# rev_002.net
KiCad netlist of a schematic drawn in EAGLE
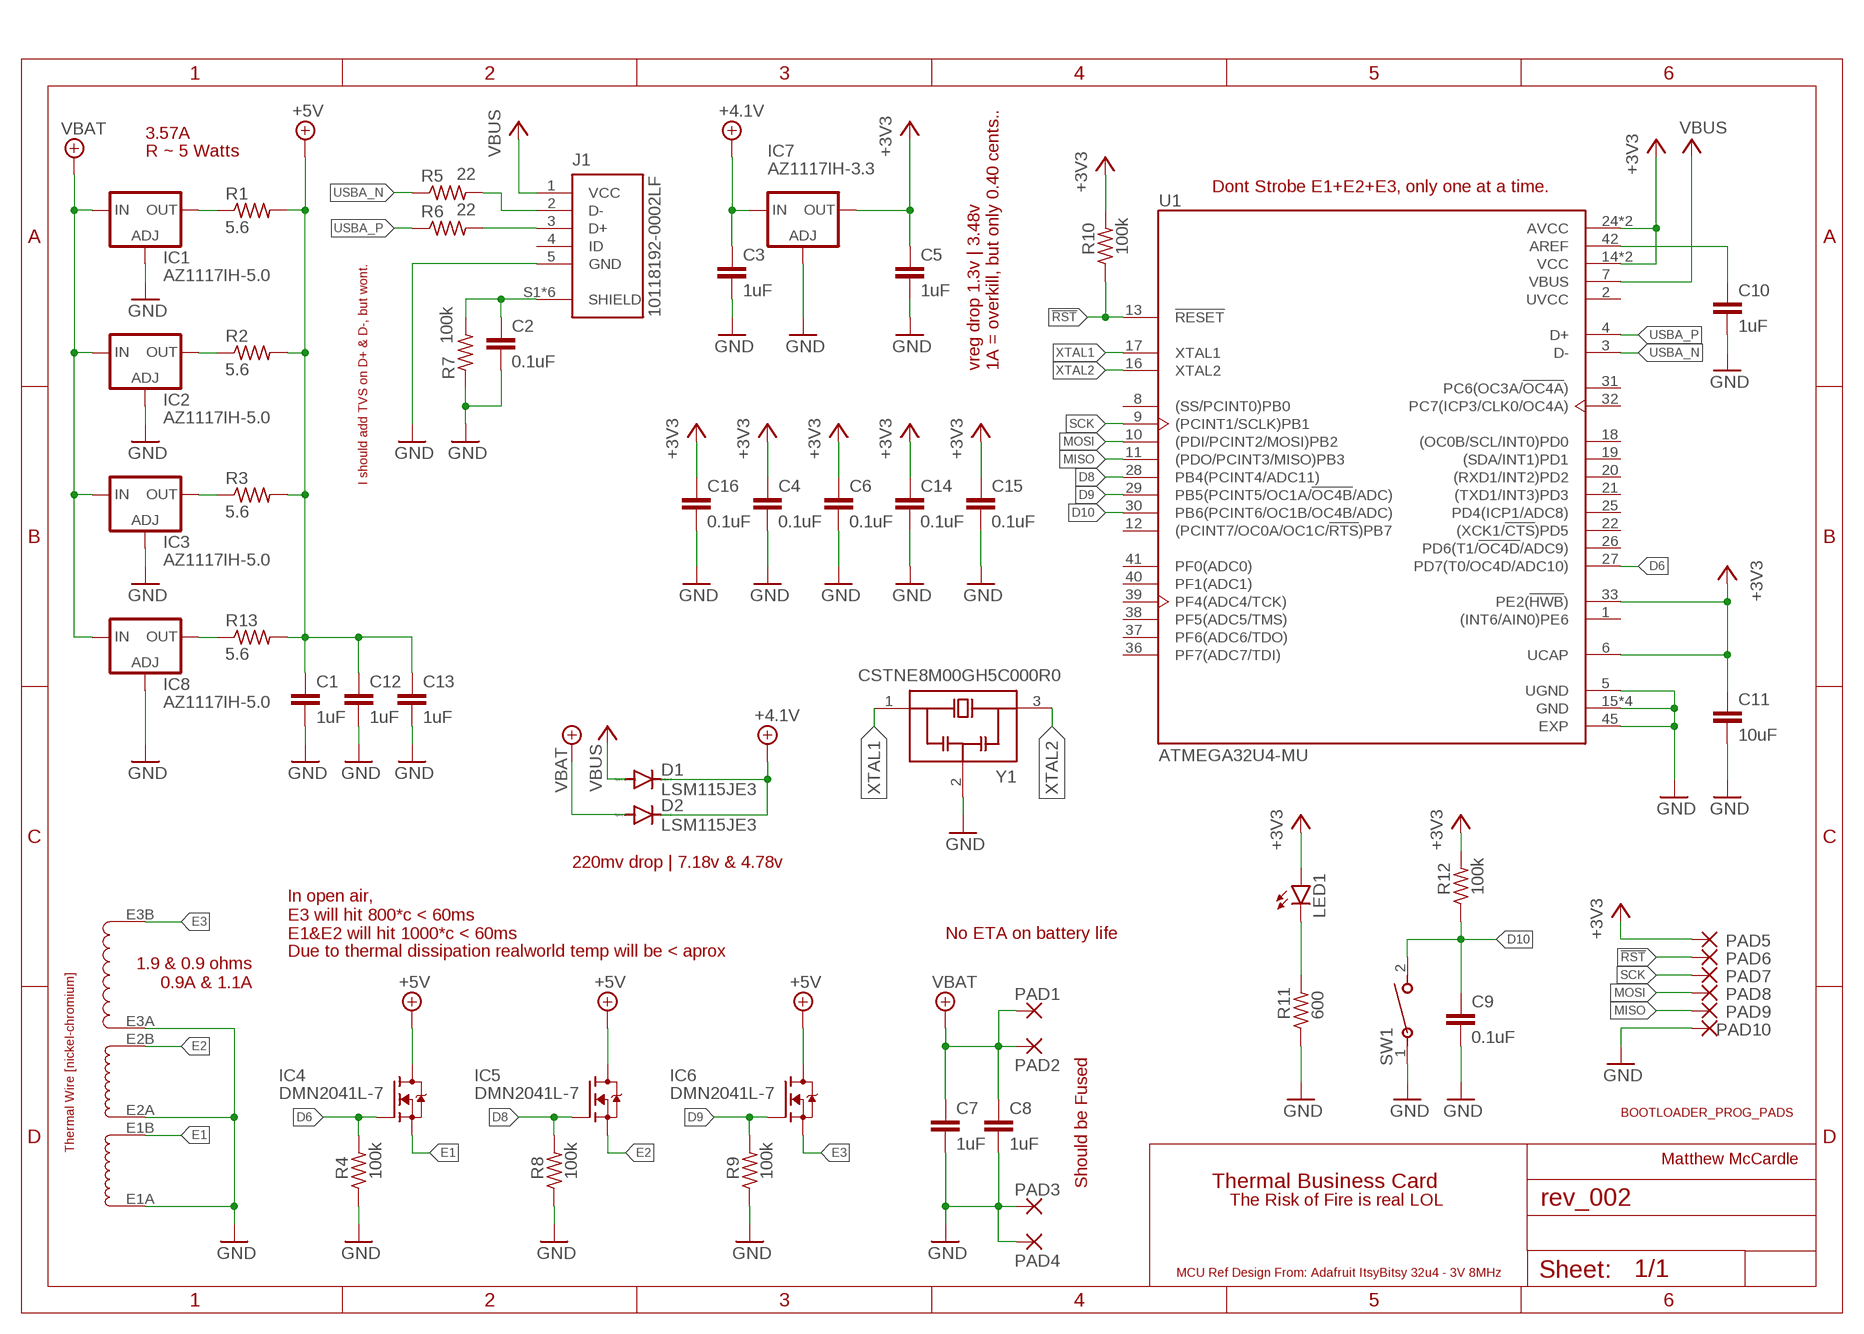
[diagram p0: schematic, sheet 1]

(export (version "E")
  (design (tool "Eeschema 10.0.6"))
  (components
    (comp (ref "C1")
      (value "1uF")
      (footprint "eagle-import:C0603")
      (libsource (lib "eagle-import") (part "C-EUC0603"))
    )
    (comp (ref "C2")
      (value "0.1uF")
      (footprint "eagle-import:C0603")
      (libsource (lib "eagle-import") (part "C-EUC0603"))
    )
    (comp (ref "C3")
      (value "1uF")
      (footprint "eagle-import:C0603")
      (libsource (lib "eagle-import") (part "C-EUC0603"))
    )
    (comp (ref "C4")
      (value "0.1uF")
      (footprint "eagle-import:C0603")
      (libsource (lib "eagle-import") (part "C-EUC0603"))
    )
    (comp (ref "C5")
      (value "1uF")
      (footprint "eagle-import:C0603")
      (libsource (lib "eagle-import") (part "C-EUC0603"))
    )
    (comp (ref "C6")
      (value "0.1uF")
      (footprint "eagle-import:C0603")
      (libsource (lib "eagle-import") (part "C-EUC0603"))
    )
    (comp (ref "C7")
      (value "1uF")
      (footprint "eagle-import:C0603")
      (libsource (lib "eagle-import") (part "C-EUC0603"))
    )
    (comp (ref "C8")
      (value "1uF")
      (footprint "eagle-import:C0603")
      (libsource (lib "eagle-import") (part "C-EUC0603"))
    )
    (comp (ref "C9")
      (value "0.1uF")
      (footprint "eagle-import:C0603")
      (libsource (lib "eagle-import") (part "C-EUC0603"))
    )
    (comp (ref "C10")
      (value "1uF")
      (footprint "eagle-import:C0603")
      (libsource (lib "eagle-import") (part "C-EUC0603"))
    )
    (comp (ref "C11")
      (value "10uF")
      (footprint "eagle-import:C0603")
      (libsource (lib "eagle-import") (part "C-EUC0603"))
    )
    (comp (ref "C12")
      (value "1uF")
      (footprint "eagle-import:C0603")
      (libsource (lib "eagle-import") (part "C-EUC0603"))
    )
    (comp (ref "C13")
      (value "1uF")
      (footprint "eagle-import:C0603")
      (libsource (lib "eagle-import") (part "C-EUC0603"))
    )
    (comp (ref "C14")
      (value "0.1uF")
      (footprint "eagle-import:C0603")
      (libsource (lib "eagle-import") (part "C-EUC0603"))
    )
    (comp (ref "C15")
      (value "0.1uF")
      (footprint "eagle-import:C0603")
      (libsource (lib "eagle-import") (part "C-EUC0603"))
    )
    (comp (ref "C16")
      (value "0.1uF")
      (footprint "eagle-import:C0603")
      (libsource (lib "eagle-import") (part "C-EUC0603"))
    )
    (comp (ref "D1")
      (value "LSM115JE3")
      (footprint "eagle-import:DO214BA")
      (libsource (lib "eagle-import") (part "DIODE-DO214BA"))
    )
    (comp (ref "D2")
      (value "LSM115JE3")
      (footprint "eagle-import:DO214BA")
      (libsource (lib "eagle-import") (part "DIODE-DO214BA"))
    )
    (comp (ref "IC1")
      (value "AZ1117IH-5.0")
      (footprint "eagle-import:SOT223")
      (libsource (lib "eagle-import") (part "AZ1117IH"))
    )
    (comp (ref "IC2")
      (value "AZ1117IH-5.0")
      (footprint "eagle-import:SOT223")
      (libsource (lib "eagle-import") (part "AZ1117IH"))
    )
    (comp (ref "IC3")
      (value "AZ1117IH-5.0")
      (footprint "eagle-import:SOT223")
      (libsource (lib "eagle-import") (part "AZ1117IH"))
    )
    (comp (ref "IC4")
      (value "DMN2041L-7")
      (footprint "eagle-import:SOT23")
      (libsource (lib "eagle-import") (part "DS31126"))
    )
    (comp (ref "IC5")
      (value "DMN2041L-7")
      (footprint "eagle-import:SOT23")
      (libsource (lib "eagle-import") (part "DS31126"))
    )
    (comp (ref "IC6")
      (value "DMN2041L-7")
      (footprint "eagle-import:SOT23")
      (libsource (lib "eagle-import") (part "DS31126"))
    )
    (comp (ref "IC7")
      (value "AZ1117IH-3.3")
      (footprint "eagle-import:SOT223")
      (libsource (lib "eagle-import") (part "AZ1117IH"))
    )
    (comp (ref "IC8")
      (value "AZ1117IH-5.0")
      (footprint "eagle-import:SOT223")
      (libsource (lib "eagle-import") (part "AZ1117IH"))
    )
    (comp (ref "J1")
      (value "10118192-0002LF")
      (footprint "eagle-import:AMPHENOL_10118192-0002LF")
      (fields (field (name "DIGI-KEY_PART_NUMBER") "609-5379-1-ND") (field (name "MF") "Amphenol ICC (FCI)"))
      (libsource (lib "eagle-import") (part "10118192-0002LF"))
    )
    (comp (ref "LED1")
      (value "LEDSML0603")
      (footprint "eagle-import:SML0603")
      (libsource (lib "eagle-import") (part "LEDSML0603"))
    )
    (comp (ref "NICR1")
      (value "HOT_WIRE")
      (footprint "eagle-import:LAYOUT_A")
      (libsource (lib "eagle-import") (part "HOT_WIRE"))
    )
    (comp (ref "PAD1")
      (value "WIREPADSMD5-2,5")
      (footprint "eagle-import:5-2,5")
      (libsource (lib "eagle-import") (part "WIREPADSMD5-2,5"))
    )
    (comp (ref "PAD2")
      (value "WIREPAD2,54/0,9")
      (footprint "eagle-import:2,54_0,9")
      (libsource (lib "eagle-import") (part "WIREPAD2,54/0,9"))
    )
    (comp (ref "PAD3")
      (value "WIREPAD2,54/0,9")
      (footprint "eagle-import:2,54_0,9")
      (libsource (lib "eagle-import") (part "WIREPAD2,54/0,9"))
    )
    (comp (ref "PAD4")
      (value "WIREPADSMD5-2,5")
      (footprint "eagle-import:5-2,5")
      (libsource (lib "eagle-import") (part "WIREPADSMD5-2,5"))
    )
    (comp (ref "PAD5")
      (value "WIREPADSMD1,27-254")
      (footprint "eagle-import:SMD1,27-2,54")
      (libsource (lib "eagle-import") (part "WIREPADSMD1,27-254"))
    )
    (comp (ref "PAD6")
      (value "WIREPADSMD1,27-254")
      (footprint "eagle-import:SMD1,27-2,54")
      (libsource (lib "eagle-import") (part "WIREPADSMD1,27-254"))
    )
    (comp (ref "PAD7")
      (value "WIREPADSMD1,27-254")
      (footprint "eagle-import:SMD1,27-2,54")
      (libsource (lib "eagle-import") (part "WIREPADSMD1,27-254"))
    )
    (comp (ref "PAD8")
      (value "WIREPADSMD1,27-254")
      (footprint "eagle-import:SMD1,27-2,54")
      (libsource (lib "eagle-import") (part "WIREPADSMD1,27-254"))
    )
    (comp (ref "PAD9")
      (value "WIREPADSMD1,27-254")
      (footprint "eagle-import:SMD1,27-2,54")
      (libsource (lib "eagle-import") (part "WIREPADSMD1,27-254"))
    )
    (comp (ref "PAD10")
      (value "WIREPADSMD1,27-254")
      (footprint "eagle-import:SMD1,27-2,54")
      (libsource (lib "eagle-import") (part "WIREPADSMD1,27-254"))
    )
    (comp (ref "R1")
      (value "5.6")
      (footprint "eagle-import:R2512")
      (libsource (lib "eagle-import") (part "R-US_R2512"))
    )
    (comp (ref "R2")
      (value "5.6")
      (footprint "eagle-import:R2512")
      (libsource (lib "eagle-import") (part "R-US_R2512"))
    )
    (comp (ref "R3")
      (value "5.6")
      (footprint "eagle-import:R2512")
      (libsource (lib "eagle-import") (part "R-US_R2512"))
    )
    (comp (ref "R4")
      (value "100k")
      (footprint "eagle-import:R0603")
      (libsource (lib "eagle-import") (part "R-US_R0603"))
    )
    (comp (ref "R5")
      (value "22")
      (footprint "eagle-import:R0603")
      (libsource (lib "eagle-import") (part "R-US_R0603"))
    )
    (comp (ref "R6")
      (value "22")
      (footprint "eagle-import:R0603")
      (libsource (lib "eagle-import") (part "R-US_R0603"))
    )
    (comp (ref "R7")
      (value "100k")
      (footprint "eagle-import:R0603")
      (libsource (lib "eagle-import") (part "R-US_R0603"))
    )
    (comp (ref "R8")
      (value "100k")
      (footprint "eagle-import:R0603")
      (libsource (lib "eagle-import") (part "R-US_R0603"))
    )
    (comp (ref "R9")
      (value "100k")
      (footprint "eagle-import:R0603")
      (libsource (lib "eagle-import") (part "R-US_R0603"))
    )
    (comp (ref "R10")
      (value "100k")
      (footprint "eagle-import:R0603")
      (libsource (lib "eagle-import") (part "R-US_R0603"))
    )
    (comp (ref "R11")
      (value "600")
      (footprint "eagle-import:R0603")
      (libsource (lib "eagle-import") (part "R-US_R0603"))
    )
    (comp (ref "R12")
      (value "100k")
      (footprint "eagle-import:R0603")
      (libsource (lib "eagle-import") (part "R-US_R0603"))
    )
    (comp (ref "R13")
      (value "5.6")
      (footprint "eagle-import:R2512")
      (libsource (lib "eagle-import") (part "R-US_R2512"))
    )
    (comp (ref "SW1")
      (value "B3AL-1000P")
      (footprint "eagle-import:SW_B3AL_OMR")
      (fields (field (name "COPYRIGHT") "Copyright (C) 2021 Ultra Librarian. All rights reserved."))
      (libsource (lib "eagle-import") (part "B3AL-1000P"))
    )
    (comp (ref "U1")
      (value "ATMEGA32U4-MU")
      (footprint "eagle-import:QFN50P700X700X100-45N")
      (fields
        (field (name "DIGI-KEY_PART_NUMBER") "2156-ATMEGA32U4-MUR-ND")
        (field (name "MF") "Microchip Technology / Atmel")
      )
      (libsource (lib "eagle-import") (part "ATMEGA32U4-MU"))
    )
    (comp (ref "Y1")
      (value "CSTNE8M00GH5C000R0")
      (footprint "eagle-import:OSC_CSTNE8M00GH5C000R0")
      (fields (field (name "DIGI-KEY_PART_NUMBER") "490-17961-1-ND") (field (name "MF") "Murata"))
      (libsource (lib "eagle-import") (part "CSTNE8M00GH5C000R0"))
    )
  )
  (nets
    (net (code "1") (name "+3V3") (class "Default")
      (node (ref "C11") (pin "1") (pinfunction "1_1") (pintype "passive"))
      (node (ref "C14") (pin "1") (pinfunction "1_1") (pintype "passive"))
      (node (ref "C15") (pin "1") (pinfunction "1_1") (pintype "passive"))
      (node (ref "C16") (pin "1") (pinfunction "1_1") (pintype "passive"))
      (node (ref "C4") (pin "1") (pinfunction "1_1") (pintype "passive"))
      (node (ref "C5") (pin "1") (pinfunction "1_1") (pintype "passive"))
      (node (ref "C6") (pin "1") (pinfunction "1_1") (pintype "passive"))
      (node (ref "IC7") (pin "2") (pinfunction "OUT_2") (pintype "passive"))
      (node (ref "IC7") (pin "4") (pinfunction "OUT_4") (pintype "passive"))
      (node (ref "LED1") (pin "A") (pinfunction "A_A") (pintype "passive"))
      (node (ref "PAD5") (pin "1") (pinfunction "P_1") (pintype "passive"))
      (node (ref "R10") (pin "2") (pinfunction "2_2") (pintype "passive"))
      (node (ref "R12") (pin "2") (pinfunction "2_2") (pintype "passive"))
      (node (ref "U1") (pin "14") (pinfunction "VCC_14") (pintype "power_in"))
      (node (ref "U1") (pin "24") (pinfunction "AVCC_24") (pintype "power_in"))
      (node (ref "U1") (pin "33") (pinfunction "PE2(~{HWB})_33") (pintype "bidirectional"))
      (node (ref "U1") (pin "34") (pinfunction "VCC_34") (pintype "power_in"))
      (node (ref "U1") (pin "44") (pinfunction "AVCC_44") (pintype "power_in"))
      (node (ref "U1") (pin "6") (pinfunction "UCAP_6") (pintype "passive"))
    )
    (net (code "2") (name "+4.1V") (class "Default")
      (node (ref "C3") (pin "1") (pinfunction "1_1") (pintype "passive"))
      (node (ref "D1") (pin "C") (pinfunction "C_C") (pintype "passive"))
      (node (ref "D2") (pin "C") (pinfunction "C_C") (pintype "passive"))
      (node (ref "IC7") (pin "3") (pinfunction "IN_3") (pintype "input"))
    )
    (net (code "3") (name "+5V") (class "Default")
      (node (ref "C1") (pin "1") (pinfunction "1_1") (pintype "passive"))
      (node (ref "C12") (pin "1") (pinfunction "1_1") (pintype "passive"))
      (node (ref "C13") (pin "1") (pinfunction "1_1") (pintype "passive"))
      (node (ref "IC4") (pin "D") (pinfunction "D_D") (pintype "passive"))
      (node (ref "IC5") (pin "D") (pinfunction "D_D") (pintype "passive"))
      (node (ref "IC6") (pin "D") (pinfunction "D_D") (pintype "passive"))
      (node (ref "R1") (pin "2") (pinfunction "2_2") (pintype "passive"))
      (node (ref "R13") (pin "2") (pinfunction "2_2") (pintype "passive"))
      (node (ref "R2") (pin "2") (pinfunction "2_2") (pintype "passive"))
      (node (ref "R3") (pin "2") (pinfunction "2_2") (pintype "passive"))
    )
    (net (code "4") (name "/UVCC") (class "Default")
      (node (ref "U1") (pin "2") (pinfunction "UVCC_2") (pintype "power_in"))
    )
    (net (code "5") (name "/~{RST}") (class "Default")
      (node (ref "PAD6") (pin "1") (pinfunction "P_1") (pintype "passive"))
      (node (ref "R10") (pin "1") (pinfunction "1_1") (pintype "passive"))
      (node (ref "U1") (pin "13") (pinfunction "~{RESET}_13") (pintype "input"))
    )
    (net (code "6") (name "D6") (class "Default")
      (node (ref "IC4") (pin "G") (pinfunction "G_G") (pintype "passive"))
      (node (ref "R4") (pin "2") (pinfunction "2_2") (pintype "passive"))
      (node (ref "U1") (pin "27") (pinfunction "PD7(T0/OC4D/ADC10)_27") (pintype "bidirectional"))
    )
    (net (code "7") (name "D8") (class "Default")
      (node (ref "IC5") (pin "G") (pinfunction "G_G") (pintype "passive"))
      (node (ref "R8") (pin "2") (pinfunction "2_2") (pintype "passive"))
      (node (ref "U1") (pin "28") (pinfunction "PB4(PCINT4/ADC11)_28") (pintype "bidirectional"))
    )
    (net (code "8") (name "D9") (class "Default")
      (node (ref "IC6") (pin "G") (pinfunction "G_G") (pintype "passive"))
      (node (ref "R9") (pin "2") (pinfunction "2_2") (pintype "passive"))
      (node (ref "U1") (pin "29") (pinfunction "PB5(PCINT5/OC1A/~{OC4B}/ADC)_29") (pintype "bidirectional"))
    )
    (net (code "9") (name "D10") (class "Default")
      (node (ref "C9") (pin "1") (pinfunction "1_1") (pintype "passive"))
      (node (ref "R12") (pin "1") (pinfunction "1_1") (pintype "passive"))
      (node (ref "SW1") (pin "2") (pinfunction "2_2") (pintype "passive"))
      (node (ref "U1") (pin "30") (pinfunction "PB6(PCINT6/OC1B/OC4B/ADC)_30") (pintype "bidirectional"))
    )
    (net (code "10") (name "E1") (class "Default")
      (node (ref "IC4") (pin "S") (pinfunction "S_S") (pintype "passive"))
      (node (ref "NICR1") (pin "E1B") (pinfunction "P$2_E1B") (pintype "bidirectional"))
    )
    (net (code "11") (name "E2") (class "Default")
      (node (ref "IC5") (pin "S") (pinfunction "S_S") (pintype "passive"))
      (node (ref "NICR1") (pin "E2B") (pinfunction "P$2_E2B") (pintype "bidirectional"))
    )
    (net (code "12") (name "E3") (class "Default")
      (node (ref "IC6") (pin "S") (pinfunction "S_S") (pintype "passive"))
      (node (ref "NICR1") (pin "E3B") (pinfunction "P$2_E3B") (pintype "bidirectional"))
    )
    (net (code "13") (name "GND") (class "Default")
      (node (ref "C1") (pin "2") (pinfunction "2_2") (pintype "passive"))
      (node (ref "C10") (pin "2") (pinfunction "2_2") (pintype "passive"))
      (node (ref "C11") (pin "2") (pinfunction "2_2") (pintype "passive"))
      (node (ref "C12") (pin "2") (pinfunction "2_2") (pintype "passive"))
      (node (ref "C13") (pin "2") (pinfunction "2_2") (pintype "passive"))
      (node (ref "C14") (pin "2") (pinfunction "2_2") (pintype "passive"))
      (node (ref "C15") (pin "2") (pinfunction "2_2") (pintype "passive"))
      (node (ref "C16") (pin "2") (pinfunction "2_2") (pintype "passive"))
      (node (ref "C2") (pin "2") (pinfunction "2_2") (pintype "passive"))
      (node (ref "C3") (pin "2") (pinfunction "2_2") (pintype "passive"))
      (node (ref "C4") (pin "2") (pinfunction "2_2") (pintype "passive"))
      (node (ref "C5") (pin "2") (pinfunction "2_2") (pintype "passive"))
      (node (ref "C6") (pin "2") (pinfunction "2_2") (pintype "passive"))
      (node (ref "C7") (pin "2") (pinfunction "2_2") (pintype "passive"))
      (node (ref "C8") (pin "2") (pinfunction "2_2") (pintype "passive"))
      (node (ref "C9") (pin "2") (pinfunction "2_2") (pintype "passive"))
      (node (ref "IC1") (pin "1") (pinfunction "ADJ_1") (pintype "input"))
      (node (ref "IC2") (pin "1") (pinfunction "ADJ_1") (pintype "input"))
      (node (ref "IC3") (pin "1") (pinfunction "ADJ_1") (pintype "input"))
      (node (ref "IC7") (pin "1") (pinfunction "ADJ_1") (pintype "input"))
      (node (ref "IC8") (pin "1") (pinfunction "ADJ_1") (pintype "input"))
      (node (ref "J1") (pin "5") (pinfunction "GND_5") (pintype "power_in"))
      (node (ref "NICR1") (pin "E1A") (pinfunction "P$1_E1A") (pintype "bidirectional"))
      (node (ref "NICR1") (pin "E2A") (pinfunction "P$1_E2A") (pintype "bidirectional"))
      (node (ref "NICR1") (pin "E3A") (pinfunction "P$1_E3A") (pintype "bidirectional"))
      (node (ref "PAD10") (pin "1") (pinfunction "P_1") (pintype "passive"))
      (node (ref "PAD3") (pin "1") (pinfunction "P_1") (pintype "passive"))
      (node (ref "PAD4") (pin "1") (pinfunction "P_1") (pintype "passive"))
      (node (ref "R11") (pin "1") (pinfunction "1_1") (pintype "passive"))
      (node (ref "R4") (pin "1") (pinfunction "1_1") (pintype "passive"))
      (node (ref "R7") (pin "1") (pinfunction "1_1") (pintype "passive"))
      (node (ref "R8") (pin "1") (pinfunction "1_1") (pintype "passive"))
      (node (ref "R9") (pin "1") (pinfunction "1_1") (pintype "passive"))
      (node (ref "SW1") (pin "1") (pinfunction "1_1") (pintype "passive"))
      (node (ref "U1") (pin "15") (pinfunction "GND_15") (pintype "power_in"))
      (node (ref "U1") (pin "23") (pinfunction "GND_23") (pintype "power_in"))
      (node (ref "U1") (pin "35") (pinfunction "GND_35") (pintype "power_in"))
      (node (ref "U1") (pin "43") (pinfunction "GND_43") (pintype "power_in"))
      (node (ref "U1") (pin "45") (pinfunction "EXP_45") (pintype "passive"))
      (node (ref "U1") (pin "5") (pinfunction "UGND_5") (pintype "power_in"))
      (node (ref "Y1") (pin "2") (pinfunction "GND_2") (pintype "power_in"))
    )
    (net (code "14") (name "MISO") (class "Default")
      (node (ref "PAD9") (pin "1") (pinfunction "P_1") (pintype "passive"))
      (node (ref "U1") (pin "11") (pinfunction "(PDO/PCINT3/MISO)PB3_11") (pintype "bidirectional"))
    )
    (net (code "15") (name "MOSI") (class "Default")
      (node (ref "PAD8") (pin "1") (pinfunction "P_1") (pintype "passive"))
      (node (ref "U1") (pin "10") (pinfunction "(PDI/PCINT2/MOSI)PB2_10") (pintype "bidirectional"))
    )
    (net (code "16") (name "Net-(C2-Pad1)") (class "Default")
      (node (ref "C2") (pin "1") (pinfunction "1_1") (pintype "passive"))
      (node (ref "J1") (pin "S1") (pinfunction "SHIELD_S1") (pintype "passive"))
      (node (ref "J1") (pin "S2") (pinfunction "SHIELD_S2") (pintype "passive"))
      (node (ref "J1") (pin "S3") (pinfunction "SHIELD_S3") (pintype "passive"))
      (node (ref "J1") (pin "S4") (pinfunction "SHIELD_S4") (pintype "passive"))
      (node (ref "J1") (pin "S5") (pinfunction "SHIELD_S5") (pintype "passive"))
      (node (ref "J1") (pin "S6") (pinfunction "SHIELD_S6") (pintype "passive"))
      (node (ref "R7") (pin "2") (pinfunction "2_2") (pintype "passive"))
    )
    (net (code "17") (name "Net-(IC1-OUT-Pad2)") (class "Default")
      (node (ref "IC1") (pin "2") (pinfunction "OUT_2") (pintype "passive"))
      (node (ref "IC1") (pin "4") (pinfunction "OUT_4") (pintype "passive"))
      (node (ref "R1") (pin "1") (pinfunction "1_1") (pintype "passive"))
    )
    (net (code "18") (name "Net-(IC2-OUT-Pad2)") (class "Default")
      (node (ref "IC2") (pin "2") (pinfunction "OUT_2") (pintype "passive"))
      (node (ref "IC2") (pin "4") (pinfunction "OUT_4") (pintype "passive"))
      (node (ref "R2") (pin "1") (pinfunction "1_1") (pintype "passive"))
    )
    (net (code "19") (name "Net-(IC3-OUT-Pad2)") (class "Default")
      (node (ref "IC3") (pin "2") (pinfunction "OUT_2") (pintype "passive"))
      (node (ref "IC3") (pin "4") (pinfunction "OUT_4") (pintype "passive"))
      (node (ref "R3") (pin "1") (pinfunction "1_1") (pintype "passive"))
    )
    (net (code "20") (name "Net-(IC8-OUT-Pad2)") (class "Default")
      (node (ref "IC8") (pin "2") (pinfunction "OUT_2") (pintype "passive"))
      (node (ref "IC8") (pin "4") (pinfunction "OUT_4") (pintype "passive"))
      (node (ref "R13") (pin "1") (pinfunction "1_1") (pintype "passive"))
    )
    (net (code "21") (name "Net-(J1-D+)") (class "Default")
      (node (ref "J1") (pin "3") (pinfunction "D+_3") (pintype "bidirectional"))
      (node (ref "R6") (pin "2") (pinfunction "2_2") (pintype "passive"))
    )
    (net (code "22") (name "Net-(J1-D-)") (class "Default")
      (node (ref "J1") (pin "2") (pinfunction "D-_2") (pintype "bidirectional"))
      (node (ref "R5") (pin "2") (pinfunction "2_2") (pintype "passive"))
    )
    (net (code "23") (name "Net-(LED1-PadC)") (class "Default")
      (node (ref "LED1") (pin "C") (pinfunction "C_C") (pintype "passive"))
      (node (ref "R11") (pin "2") (pinfunction "2_2") (pintype "passive"))
    )
    (net (code "24") (name "Net-(U1-AREF)") (class "Default")
      (node (ref "C10") (pin "1") (pinfunction "1_1") (pintype "passive"))
      (node (ref "U1") (pin "42") (pinfunction "AREF_42") (pintype "power_in"))
    )
    (net (code "25") (name "SCK") (class "Default")
      (node (ref "PAD7") (pin "1") (pinfunction "P_1") (pintype "passive"))
      (node (ref "U1") (pin "9") (pinfunction "(PCINT1/SCLK)PB1_9") (pintype "bidirectional"))
    )
    (net (code "26") (name "USBA_N") (class "Default")
      (node (ref "R5") (pin "1") (pinfunction "1_1") (pintype "passive"))
      (node (ref "U1") (pin "3") (pinfunction "D-_3") (pintype "bidirectional"))
    )
    (net (code "27") (name "USBA_P") (class "Default")
      (node (ref "R6") (pin "1") (pinfunction "1_1") (pintype "passive"))
      (node (ref "U1") (pin "4") (pinfunction "D+_4") (pintype "bidirectional"))
    )
    (net (code "28") (name "VBAT") (class "Default")
      (node (ref "C7") (pin "1") (pinfunction "1_1") (pintype "passive"))
      (node (ref "C8") (pin "1") (pinfunction "1_1") (pintype "passive"))
      (node (ref "D2") (pin "A") (pinfunction "A_A") (pintype "passive"))
      (node (ref "IC1") (pin "3") (pinfunction "IN_3") (pintype "input"))
      (node (ref "IC2") (pin "3") (pinfunction "IN_3") (pintype "input"))
      (node (ref "IC3") (pin "3") (pinfunction "IN_3") (pintype "input"))
      (node (ref "IC8") (pin "3") (pinfunction "IN_3") (pintype "input"))
      (node (ref "PAD1") (pin "1") (pinfunction "P_1") (pintype "passive"))
      (node (ref "PAD2") (pin "1") (pinfunction "P_1") (pintype "passive"))
    )
    (net (code "29") (name "VBUS") (class "Default")
      (node (ref "D1") (pin "A") (pinfunction "A_A") (pintype "passive"))
      (node (ref "J1") (pin "1") (pinfunction "VCC_1") (pintype "power_in"))
      (node (ref "U1") (pin "7") (pinfunction "VBUS_7") (pintype "power_in"))
    )
    (net (code "30") (name "XTAL1") (class "Default")
      (node (ref "U1") (pin "17") (pinfunction "XTAL1_17") (pintype "input"))
      (node (ref "Y1") (pin "1") (pinfunction "IN_1") (pintype "input"))
    )
    (net (code "31") (name "XTAL2") (class "Default")
      (node (ref "U1") (pin "16") (pinfunction "XTAL2_16") (pintype "output"))
      (node (ref "Y1") (pin "3") (pinfunction "OUT_3") (pintype "output"))
    )
    (net (code "32") (name "unconnected-(J1-ID-Pad4)") (class "Default")
      (node (ref "J1") (pin "4") (pinfunction "ID_4") (pintype "bidirectional"))
    )
    (net (code "33") (name "unconnected-(U1-(INT6{slash}AIN0)PE6-Pad1)") (class "Default")
      (node (ref "U1") (pin "1") (pinfunction "(INT6/AIN0)PE6_1") (pintype "bidirectional"))
    )
    (net (code "34") (name "unconnected-(U1-(OC0B{slash}SCL{slash}INT0)PD0-Pad18)") (class "Default")
      (node (ref "U1") (pin "18") (pinfunction "(OC0B/SCL/INT0)PD0_18") (pintype "bidirectional"))
    )
    (net (code "35") (name "unconnected-(U1-(PCINT7{slash}OC0A{slash}OC1C{slash}~{RTS})PB7-Pad12)") (class "Default")
      (node (ref "U1") (pin "12") (pinfunction "(PCINT7/OC0A/OC1C/~{RTS})PB7_12") (pintype "bidirectional"))
    )
    (net (code "36") (name "unconnected-(U1-(RXD1{slash}INT2)PD2-Pad20)") (class "Default")
      (node (ref "U1") (pin "20") (pinfunction "(RXD1/INT2)PD2_20") (pintype "bidirectional"))
    )
    (net (code "37") (name "unconnected-(U1-(SDA{slash}INT1)PD1-Pad19)") (class "Default")
      (node (ref "U1") (pin "19") (pinfunction "(SDA/INT1)PD1_19") (pintype "bidirectional"))
    )
    (net (code "38") (name "unconnected-(U1-(SS{slash}PCINT0)PB0-Pad8)") (class "Default")
      (node (ref "U1") (pin "8") (pinfunction "(SS/PCINT0)PB0_8") (pintype "bidirectional"))
    )
    (net (code "39") (name "unconnected-(U1-(TXD1{slash}INT3)PD3-Pad21)") (class "Default")
      (node (ref "U1") (pin "21") (pinfunction "(TXD1/INT3)PD3_21") (pintype "bidirectional"))
    )
    (net (code "40") (name "unconnected-(U1-(XCK1{slash}~{CTS})PD5-Pad22)") (class "Default")
      (node (ref "U1") (pin "22") (pinfunction "(XCK1/~{CTS})PD5_22") (pintype "bidirectional"))
    )
    (net (code "41") (name "unconnected-(U1-PC6(OC3A{slash}~{OC4A})-Pad31)") (class "Default")
      (node (ref "U1") (pin "31") (pinfunction "PC6(OC3A/~{OC4A})_31") (pintype "bidirectional"))
    )
    (net (code "42") (name "unconnected-(U1-PC7(ICP3{slash}CLK0{slash}OC4A)-Pad32)") (class "Default")
      (node (ref "U1") (pin "32") (pinfunction "PC7(ICP3/CLK0/OC4A)_32") (pintype "bidirectional"))
    )
    (net (code "43") (name "unconnected-(U1-PD4(ICP1{slash}ADC8)-Pad25)") (class "Default")
      (node (ref "U1") (pin "25") (pinfunction "PD4(ICP1/ADC8)_25") (pintype "bidirectional"))
    )
    (net (code "44") (name "unconnected-(U1-PD6(T1{slash}~{OC4D}{slash}ADC9)-Pad26)") (class "Default")
      (node (ref "U1") (pin "26") (pinfunction "PD6(T1/~{OC4D}/ADC9)_26") (pintype "bidirectional"))
    )
    (net (code "45") (name "unconnected-(U1-PF0(ADC0)-Pad41)") (class "Default")
      (node (ref "U1") (pin "41") (pinfunction "PF0(ADC0)_41") (pintype "bidirectional"))
    )
    (net (code "46") (name "unconnected-(U1-PF1(ADC1)-Pad40)") (class "Default")
      (node (ref "U1") (pin "40") (pinfunction "PF1(ADC1)_40") (pintype "bidirectional"))
    )
    (net (code "47") (name "unconnected-(U1-PF4(ADC4{slash}TCK)-Pad39)") (class "Default")
      (node (ref "U1") (pin "39") (pinfunction "PF4(ADC4/TCK)_39") (pintype "bidirectional"))
    )
    (net (code "48") (name "unconnected-(U1-PF5(ADC5{slash}TMS)-Pad38)") (class "Default")
      (node (ref "U1") (pin "38") (pinfunction "PF5(ADC5/TMS)_38") (pintype "bidirectional"))
    )
    (net (code "49") (name "unconnected-(U1-PF6(ADC6{slash}TDO)-Pad37)") (class "Default")
      (node (ref "U1") (pin "37") (pinfunction "PF6(ADC6/TDO)_37") (pintype "bidirectional"))
    )
    (net (code "50") (name "unconnected-(U1-PF7(ADC7{slash}TDI)-Pad36)") (class "Default")
      (node (ref "U1") (pin "36") (pinfunction "PF7(ADC7/TDI)_36") (pintype "bidirectional"))
    )
  )
)
